# Brick_Doc_02.net
KiCad netlist of a schematic drawn in EAGLE
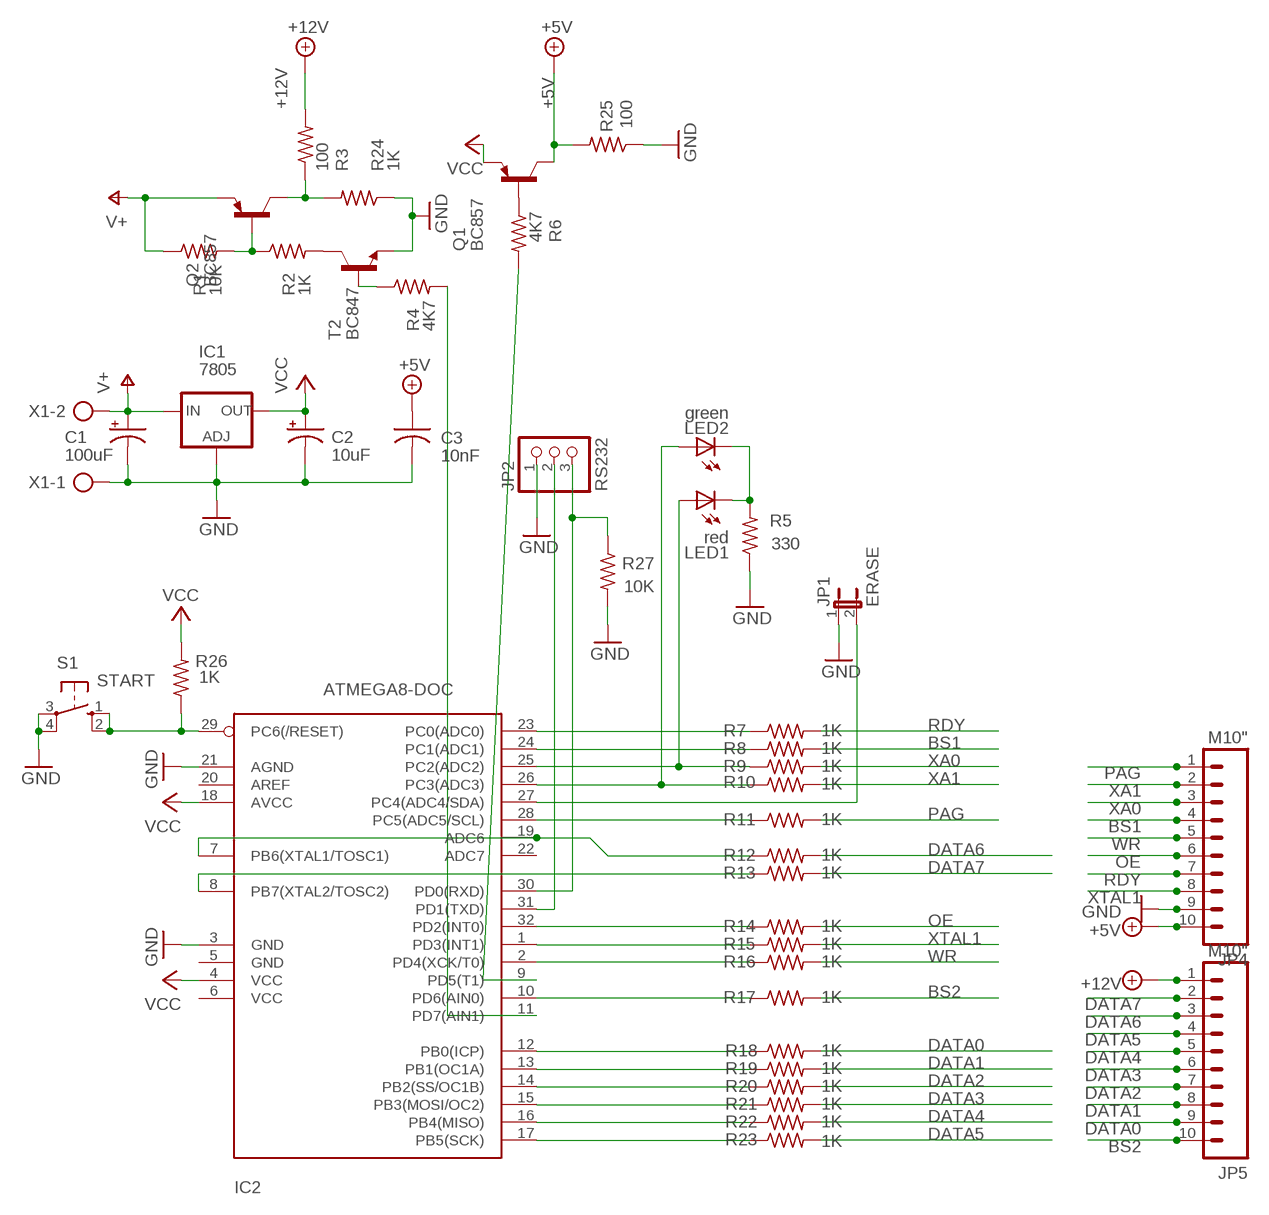
[diagram p0: schematic, sheet 1]

(export (version "E")
  (design (tool "Eeschema 10.0.6"))
  (components
    (comp (ref "C1")
      (value "100uF")
      (footprint "eagle-import:EIA3216")
      (libsource (lib "eagle-import") (part "CAP_POL1206"))
    )
    (comp (ref "C2")
      (value "10uF")
      (footprint "eagle-import:EIA3216")
      (libsource (lib "eagle-import") (part "CAP_POL1206"))
    )
    (comp (ref "C3")
      (value "10nF")
      (footprint "eagle-import:C0805")
      (libsource (lib "eagle-import") (part "C-USC0805"))
    )
    (comp (ref "IC1")
      (value "7805")
      (footprint "eagle-import:V-REG_DPACK")
      (libsource (lib "eagle-import") (part "V_REG_317DPACK"))
    )
    (comp (ref "IC2")
      (value "ATMEGA8-DOC")
      (footprint "eagle-import:TQFP32-08")
      (libsource (lib "eagle-import") (part "AVR-MEGA8-AI"))
    )
    (comp (ref "JP1")
      (value "ERASE")
      (footprint "eagle-import:JP1")
      (libsource (lib "eagle-import") (part "JP1E"))
    )
    (comp (ref "JP2")
      (value "RS232")
      (footprint "eagle-import:1X03")
      (libsource (lib "eagle-import") (part "PINHD-1X3"))
    )
    (comp (ref "JP4")
      (value "M10\"")
      (footprint "eagle-import:1X10")
      (libsource (lib "eagle-import") (part "M10{dblquote}"))
    )
    (comp (ref "JP5")
      (value "M10\"")
      (footprint "eagle-import:1X10")
      (libsource (lib "eagle-import") (part "M10{dblquote}"))
    )
    (comp (ref "LED1")
      (value "red")
      (footprint "eagle-import:SML0603")
      (libsource (lib "eagle-import") (part "LEDSML0603"))
    )
    (comp (ref "LED2")
      (value "green")
      (footprint "eagle-import:SML0603")
      (libsource (lib "eagle-import") (part "LEDSML0603"))
    )
    (comp (ref "Q1")
      (value "BC857")
      (footprint "eagle-import:SOT23-BEC")
      (libsource (lib "eagle-import") (part "BC857SMDALT1"))
    )
    (comp (ref "Q2")
      (value "BC857")
      (footprint "eagle-import:SOT23-BEC")
      (libsource (lib "eagle-import") (part "BC857SMDALT1"))
    )
    (comp (ref "R1")
      (value "10K")
      (footprint "eagle-import:R0805")
      (libsource (lib "eagle-import") (part "R-US_R0805"))
    )
    (comp (ref "R2")
      (value "1K")
      (footprint "eagle-import:R0805")
      (libsource (lib "eagle-import") (part "R-US_R0805"))
    )
    (comp (ref "R3")
      (value "100")
      (footprint "eagle-import:R0805")
      (libsource (lib "eagle-import") (part "R-US_R0805"))
    )
    (comp (ref "R4")
      (value "4K7")
      (footprint "eagle-import:R0805")
      (libsource (lib "eagle-import") (part "R-US_R0805"))
    )
    (comp (ref "R5")
      (value "330")
      (footprint "eagle-import:R0805")
      (libsource (lib "eagle-import") (part "R-US_R0805"))
    )
    (comp (ref "R6")
      (value "4K7")
      (footprint "eagle-import:R0805")
      (libsource (lib "eagle-import") (part "R-US_R0805"))
    )
    (comp (ref "R7")
      (value "1K")
      (footprint "eagle-import:R0805")
      (libsource (lib "eagle-import") (part "R-US_R0805"))
    )
    (comp (ref "R8")
      (value "1K")
      (footprint "eagle-import:R0805")
      (libsource (lib "eagle-import") (part "R-US_R0805"))
    )
    (comp (ref "R9")
      (value "1K")
      (footprint "eagle-import:R0805")
      (libsource (lib "eagle-import") (part "R-US_R0805"))
    )
    (comp (ref "R10")
      (value "1K")
      (footprint "eagle-import:R0805")
      (libsource (lib "eagle-import") (part "R-US_R0805"))
    )
    (comp (ref "R11")
      (value "1K")
      (footprint "eagle-import:R0805")
      (libsource (lib "eagle-import") (part "R-US_R0805"))
    )
    (comp (ref "R12")
      (value "1K")
      (footprint "eagle-import:R0805")
      (libsource (lib "eagle-import") (part "R-US_R0805"))
    )
    (comp (ref "R13")
      (value "1K")
      (footprint "eagle-import:R0805")
      (libsource (lib "eagle-import") (part "R-US_R0805"))
    )
    (comp (ref "R14")
      (value "1K")
      (footprint "eagle-import:R0805")
      (libsource (lib "eagle-import") (part "R-US_R0805"))
    )
    (comp (ref "R15")
      (value "1K")
      (footprint "eagle-import:R0805")
      (libsource (lib "eagle-import") (part "R-US_R0805"))
    )
    (comp (ref "R16")
      (value "1K")
      (footprint "eagle-import:R0805")
      (libsource (lib "eagle-import") (part "R-US_R0805"))
    )
    (comp (ref "R17")
      (value "1K")
      (footprint "eagle-import:R0805")
      (libsource (lib "eagle-import") (part "R-US_R0805"))
    )
    (comp (ref "R18")
      (value "1K")
      (footprint "eagle-import:R0805")
      (libsource (lib "eagle-import") (part "R-US_R0805"))
    )
    (comp (ref "R19")
      (value "1K")
      (footprint "eagle-import:R0805")
      (libsource (lib "eagle-import") (part "R-US_R0805"))
    )
    (comp (ref "R20")
      (value "1K")
      (footprint "eagle-import:R0805")
      (libsource (lib "eagle-import") (part "R-US_R0805"))
    )
    (comp (ref "R21")
      (value "1K")
      (footprint "eagle-import:R0805")
      (libsource (lib "eagle-import") (part "R-US_R0805"))
    )
    (comp (ref "R22")
      (value "1K")
      (footprint "eagle-import:R0805")
      (libsource (lib "eagle-import") (part "R-US_R0805"))
    )
    (comp (ref "R23")
      (value "1K")
      (footprint "eagle-import:R0805")
      (libsource (lib "eagle-import") (part "R-US_R0805"))
    )
    (comp (ref "R24")
      (value "1K")
      (footprint "eagle-import:R0805")
      (libsource (lib "eagle-import") (part "R-US_R0805"))
    )
    (comp (ref "R25")
      (value "100")
      (footprint "eagle-import:R0805")
      (libsource (lib "eagle-import") (part "R-US_R0805"))
    )
    (comp (ref "R26")
      (value "1K")
      (footprint "eagle-import:R0805")
      (libsource (lib "eagle-import") (part "R-US_R0805"))
    )
    (comp (ref "R27")
      (value "10K")
      (footprint "eagle-import:R0805")
      (libsource (lib "eagle-import") (part "R-US_R0805"))
    )
    (comp (ref "S1")
      (value "START")
      (footprint "eagle-import:B3F-10XX")
      (libsource (lib "eagle-import") (part "10-XX"))
    )
    (comp (ref "T2")
      (value "BC847")
      (footprint "eagle-import:SOT23")
      (libsource (lib "eagle-import") (part "BC847"))
    )
    (comp (ref "X1")
      (value "AK500/2")
      (footprint "eagle-import:AK500_2")
      (libsource (lib "eagle-import") (part "AK500/2"))
    )
  )
  (nets
    (net (code "1") (name "+5V") (class "Default")
      (node (ref "C3") (pin "1") (pinfunction "1_1") (pintype "passive"))
      (node (ref "JP4") (pin "10") (pinfunction "10_10") (pintype "passive"))
      (node (ref "Q1") (pin "C") (pinfunction "C_C") (pintype "passive"))
      (node (ref "R25") (pin "2") (pinfunction "2_2") (pintype "passive"))
    )
    (net (code "2") (name "+12V") (class "Default")
      (node (ref "JP5") (pin "1") (pinfunction "1_1") (pintype "passive"))
      (node (ref "R3") (pin "2") (pinfunction "2_2") (pintype "passive"))
    )
    (net (code "3") (name "/BS1") (class "Default")
      (node (ref "JP4") (pin "4") (pinfunction "4_4") (pintype "passive"))
      (node (ref "R8") (pin "2") (pinfunction "2_2") (pintype "passive"))
    )
    (net (code "4") (name "/BS2") (class "Default")
      (node (ref "JP5") (pin "10") (pinfunction "10_10") (pintype "passive"))
      (node (ref "R17") (pin "2") (pinfunction "2_2") (pintype "passive"))
    )
    (net (code "5") (name "/DATA0") (class "Default")
      (node (ref "JP5") (pin "9") (pinfunction "9_9") (pintype "passive"))
      (node (ref "R18") (pin "2") (pinfunction "2_2") (pintype "passive"))
    )
    (net (code "6") (name "/DATA1") (class "Default")
      (node (ref "JP5") (pin "8") (pinfunction "8_8") (pintype "passive"))
      (node (ref "R19") (pin "2") (pinfunction "2_2") (pintype "passive"))
    )
    (net (code "7") (name "/DATA2") (class "Default")
      (node (ref "JP5") (pin "7") (pinfunction "7_7") (pintype "passive"))
      (node (ref "R20") (pin "2") (pinfunction "2_2") (pintype "passive"))
    )
    (net (code "8") (name "/DATA3") (class "Default")
      (node (ref "JP5") (pin "6") (pinfunction "6_6") (pintype "passive"))
      (node (ref "R21") (pin "2") (pinfunction "2_2") (pintype "passive"))
    )
    (net (code "9") (name "/DATA4") (class "Default")
      (node (ref "JP5") (pin "5") (pinfunction "5_5") (pintype "passive"))
      (node (ref "R22") (pin "2") (pinfunction "2_2") (pintype "passive"))
    )
    (net (code "10") (name "/DATA5") (class "Default")
      (node (ref "JP5") (pin "4") (pinfunction "4_4") (pintype "passive"))
      (node (ref "R23") (pin "2") (pinfunction "2_2") (pintype "passive"))
    )
    (net (code "11") (name "/DATA6") (class "Default")
      (node (ref "JP5") (pin "3") (pinfunction "3_3") (pintype "passive"))
      (node (ref "R12") (pin "2") (pinfunction "2_2") (pintype "passive"))
    )
    (net (code "12") (name "/DATA7") (class "Default")
      (node (ref "JP5") (pin "2") (pinfunction "2_2") (pintype "passive"))
      (node (ref "R13") (pin "2") (pinfunction "2_2") (pintype "passive"))
    )
    (net (code "13") (name "/OE") (class "Default")
      (node (ref "JP4") (pin "6") (pinfunction "6_6") (pintype "passive"))
      (node (ref "R14") (pin "2") (pinfunction "2_2") (pintype "passive"))
    )
    (net (code "14") (name "/PAG") (class "Default")
      (node (ref "JP4") (pin "1") (pinfunction "1_1") (pintype "passive"))
      (node (ref "R11") (pin "2") (pinfunction "2_2") (pintype "passive"))
    )
    (net (code "15") (name "/RDY") (class "Default")
      (node (ref "JP4") (pin "7") (pinfunction "7_7") (pintype "passive"))
      (node (ref "R7") (pin "2") (pinfunction "2_2") (pintype "passive"))
    )
    (net (code "16") (name "/WR") (class "Default")
      (node (ref "JP4") (pin "5") (pinfunction "5_5") (pintype "passive"))
      (node (ref "R16") (pin "2") (pinfunction "2_2") (pintype "passive"))
    )
    (net (code "17") (name "/XA0") (class "Default")
      (node (ref "JP4") (pin "3") (pinfunction "3_3") (pintype "passive"))
      (node (ref "R9") (pin "2") (pinfunction "2_2") (pintype "passive"))
    )
    (net (code "18") (name "/XA1") (class "Default")
      (node (ref "JP4") (pin "2") (pinfunction "2_2") (pintype "passive"))
      (node (ref "R10") (pin "2") (pinfunction "2_2") (pintype "passive"))
    )
    (net (code "19") (name "/XTAL1") (class "Default")
      (node (ref "JP4") (pin "8") (pinfunction "8_8") (pintype "passive"))
      (node (ref "R15") (pin "2") (pinfunction "2_2") (pintype "passive"))
    )
    (net (code "20") (name "GND") (class "Default")
      (node (ref "C1") (pin "C") (pinfunction "-_C") (pintype "passive"))
      (node (ref "C2") (pin "C") (pinfunction "-_C") (pintype "passive"))
      (node (ref "C3") (pin "2") (pinfunction "2_2") (pintype "passive"))
      (node (ref "IC1") (pin "1") (pinfunction "ADJ_1") (pintype "input"))
      (node (ref "IC2") (pin "21") (pinfunction "AGND_21") (pintype "bidirectional"))
      (node (ref "IC2") (pin "3") (pinfunction "GND_3") (pintype "bidirectional"))
      (node (ref "JP1") (pin "1") (pinfunction "1_1") (pintype "passive"))
      (node (ref "JP2") (pin "1") (pinfunction "1_1") (pintype "passive"))
      (node (ref "JP4") (pin "9") (pinfunction "9_9") (pintype "passive"))
      (node (ref "R24") (pin "1") (pinfunction "1_1") (pintype "passive"))
      (node (ref "R25") (pin "1") (pinfunction "1_1") (pintype "passive"))
      (node (ref "R27") (pin "2") (pinfunction "2_2") (pintype "passive"))
      (node (ref "R5") (pin "1") (pinfunction "1_1") (pintype "passive"))
      (node (ref "S1") (pin "3") (pinfunction "P_3") (pintype "passive"))
      (node (ref "S1") (pin "4") (pinfunction "P1_4") (pintype "passive"))
      (node (ref "T2") (pin "2") (pinfunction "E_2") (pintype "passive"))
      (node (ref "X1") (pin "1") (pinfunction "KL_1") (pintype "passive"))
    )
    (net (code "21") (name "Net-(IC2-ADC6)") (class "Default")
      (node (ref "IC2") (pin "19") (pinfunction "ADC6_19") (pintype "bidirectional"))
      (node (ref "IC2") (pin "7") (pinfunction "PB6(XTAL1/TOSC1)_7") (pintype "bidirectional"))
      (node (ref "R12") (pin "1") (pinfunction "1_1") (pintype "passive"))
    )
    (net (code "22") (name "Net-(IC2-PB0(ICP))") (class "Default")
      (node (ref "IC2") (pin "12") (pinfunction "PB0(ICP)_12") (pintype "bidirectional"))
      (node (ref "R18") (pin "1") (pinfunction "1_1") (pintype "passive"))
    )
    (net (code "23") (name "Net-(IC2-PB1(OC1A))") (class "Default")
      (node (ref "IC2") (pin "13") (pinfunction "PB1(OC1A)_13") (pintype "bidirectional"))
      (node (ref "R19") (pin "1") (pinfunction "1_1") (pintype "passive"))
    )
    (net (code "24") (name "Net-(IC2-PB2(SS{slash}OC1B))") (class "Default")
      (node (ref "IC2") (pin "14") (pinfunction "PB2(SS/OC1B)_14") (pintype "bidirectional"))
      (node (ref "R20") (pin "1") (pinfunction "1_1") (pintype "passive"))
    )
    (net (code "25") (name "Net-(IC2-PB3(MOSI{slash}OC2))") (class "Default")
      (node (ref "IC2") (pin "15") (pinfunction "PB3(MOSI/OC2)_15") (pintype "bidirectional"))
      (node (ref "R21") (pin "1") (pinfunction "1_1") (pintype "passive"))
    )
    (net (code "26") (name "Net-(IC2-PB4(MISO))") (class "Default")
      (node (ref "IC2") (pin "16") (pinfunction "PB4(MISO)_16") (pintype "bidirectional"))
      (node (ref "R22") (pin "1") (pinfunction "1_1") (pintype "passive"))
    )
    (net (code "27") (name "Net-(IC2-PB5(SCK))") (class "Default")
      (node (ref "IC2") (pin "17") (pinfunction "PB5(SCK)_17") (pintype "bidirectional"))
      (node (ref "R23") (pin "1") (pinfunction "1_1") (pintype "passive"))
    )
    (net (code "28") (name "Net-(IC2-PB7(XTAL2{slash}TOSC2))") (class "Default")
      (node (ref "IC2") (pin "8") (pinfunction "PB7(XTAL2/TOSC2)_8") (pintype "bidirectional"))
      (node (ref "R13") (pin "1") (pinfunction "1_1") (pintype "passive"))
    )
    (net (code "29") (name "Net-(IC2-PC0(ADC0))") (class "Default")
      (node (ref "IC2") (pin "23") (pinfunction "PC0(ADC0)_23") (pintype "bidirectional"))
      (node (ref "R7") (pin "1") (pinfunction "1_1") (pintype "passive"))
    )
    (net (code "30") (name "Net-(IC2-PC1(ADC1))") (class "Default")
      (node (ref "IC2") (pin "24") (pinfunction "PC1(ADC1)_24") (pintype "bidirectional"))
      (node (ref "R8") (pin "1") (pinfunction "1_1") (pintype "passive"))
    )
    (net (code "31") (name "Net-(IC2-PC2(ADC2))") (class "Default")
      (node (ref "IC2") (pin "25") (pinfunction "PC2(ADC2)_25") (pintype "bidirectional"))
      (node (ref "LED1") (pin "A") (pinfunction "A_A") (pintype "passive"))
      (node (ref "R9") (pin "1") (pinfunction "1_1") (pintype "passive"))
    )
    (net (code "32") (name "Net-(IC2-PC3(ADC3))") (class "Default")
      (node (ref "IC2") (pin "26") (pinfunction "PC3(ADC3)_26") (pintype "bidirectional"))
      (node (ref "LED2") (pin "A") (pinfunction "A_A") (pintype "passive"))
      (node (ref "R10") (pin "1") (pinfunction "1_1") (pintype "passive"))
    )
    (net (code "33") (name "Net-(IC2-PC4(ADC4{slash}SDA))") (class "Default")
      (node (ref "IC2") (pin "27") (pinfunction "PC4(ADC4/SDA)_27") (pintype "bidirectional"))
      (node (ref "JP1") (pin "2") (pinfunction "2_2") (pintype "passive"))
    )
    (net (code "34") (name "Net-(IC2-PC5(ADC5{slash}SCL))") (class "Default")
      (node (ref "IC2") (pin "28") (pinfunction "PC5(ADC5/SCL)_28") (pintype "bidirectional"))
      (node (ref "R11") (pin "1") (pinfunction "1_1") (pintype "passive"))
    )
    (net (code "35") (name "Net-(IC2-PC6({slash}RESET))") (class "Default")
      (node (ref "IC2") (pin "29") (pinfunction "PC6(/RESET)_29") (pintype "bidirectional"))
      (node (ref "R26") (pin "1") (pinfunction "1_1") (pintype "passive"))
      (node (ref "S1") (pin "1") (pinfunction "S_1") (pintype "passive"))
      (node (ref "S1") (pin "2") (pinfunction "S1_2") (pintype "passive"))
    )
    (net (code "36") (name "Net-(IC2-PD0(RXD))") (class "Default")
      (node (ref "IC2") (pin "30") (pinfunction "PD0(RXD)_30") (pintype "bidirectional"))
      (node (ref "JP2") (pin "3") (pinfunction "3_3") (pintype "passive"))
      (node (ref "R27") (pin "1") (pinfunction "1_1") (pintype "passive"))
    )
    (net (code "37") (name "Net-(IC2-PD1(TXD))") (class "Default")
      (node (ref "IC2") (pin "31") (pinfunction "PD1(TXD)_31") (pintype "bidirectional"))
      (node (ref "JP2") (pin "2") (pinfunction "2_2") (pintype "passive"))
    )
    (net (code "38") (name "Net-(IC2-PD2(INT0))") (class "Default")
      (node (ref "IC2") (pin "32") (pinfunction "PD2(INT0)_32") (pintype "bidirectional"))
      (node (ref "R14") (pin "1") (pinfunction "1_1") (pintype "passive"))
    )
    (net (code "39") (name "Net-(IC2-PD3(INT1))") (class "Default")
      (node (ref "IC2") (pin "1") (pinfunction "PD3(INT1)_1") (pintype "bidirectional"))
      (node (ref "R15") (pin "1") (pinfunction "1_1") (pintype "passive"))
    )
    (net (code "40") (name "Net-(IC2-PD4(XCK{slash}T0))") (class "Default")
      (node (ref "IC2") (pin "2") (pinfunction "PD4(XCK/T0)_2") (pintype "bidirectional"))
      (node (ref "R16") (pin "1") (pinfunction "1_1") (pintype "passive"))
    )
    (net (code "41") (name "Net-(IC2-PD5(T1))") (class "Default")
      (node (ref "IC2") (pin "9") (pinfunction "PD5(T1)_9") (pintype "bidirectional"))
      (node (ref "R6") (pin "2") (pinfunction "2_2") (pintype "passive"))
    )
    (net (code "42") (name "Net-(IC2-PD6(AIN0))") (class "Default")
      (node (ref "IC2") (pin "10") (pinfunction "PD6(AIN0)_10") (pintype "bidirectional"))
      (node (ref "R17") (pin "1") (pinfunction "1_1") (pintype "passive"))
    )
    (net (code "43") (name "Net-(IC2-PD7(AIN1))") (class "Default")
      (node (ref "IC2") (pin "11") (pinfunction "PD7(AIN1)_11") (pintype "bidirectional"))
      (node (ref "R4") (pin "2") (pinfunction "2_2") (pintype "passive"))
    )
    (net (code "44") (name "Net-(LED1-PadC)") (class "Default")
      (node (ref "LED1") (pin "C") (pinfunction "C_C") (pintype "passive"))
      (node (ref "LED2") (pin "C") (pinfunction "C_C") (pintype "passive"))
      (node (ref "R5") (pin "2") (pinfunction "2_2") (pintype "passive"))
    )
    (net (code "45") (name "Net-(Q1-PadB)") (class "Default")
      (node (ref "Q1") (pin "B") (pinfunction "B_B") (pintype "passive"))
      (node (ref "R6") (pin "1") (pinfunction "1_1") (pintype "passive"))
    )
    (net (code "46") (name "Net-(Q2-PadB)") (class "Default")
      (node (ref "Q2") (pin "B") (pinfunction "B_B") (pintype "passive"))
      (node (ref "R1") (pin "2") (pinfunction "2_2") (pintype "passive"))
      (node (ref "R2") (pin "1") (pinfunction "1_1") (pintype "passive"))
    )
    (net (code "47") (name "Net-(Q2-PadC)") (class "Default")
      (node (ref "Q2") (pin "C") (pinfunction "C_C") (pintype "passive"))
      (node (ref "R24") (pin "2") (pinfunction "2_2") (pintype "passive"))
      (node (ref "R3") (pin "1") (pinfunction "1_1") (pintype "passive"))
    )
    (net (code "48") (name "Net-(T2-B)") (class "Default")
      (node (ref "R4") (pin "1") (pinfunction "1_1") (pintype "passive"))
      (node (ref "T2") (pin "1") (pinfunction "B_1") (pintype "passive"))
    )
    (net (code "49") (name "Net-(T2-C)") (class "Default")
      (node (ref "R2") (pin "2") (pinfunction "2_2") (pintype "passive"))
      (node (ref "T2") (pin "3") (pinfunction "C_3") (pintype "passive"))
    )
    (net (code "50") (name "V+") (class "Default")
      (node (ref "C1") (pin "A") (pinfunction "+_A") (pintype "passive"))
      (node (ref "IC1") (pin "3") (pinfunction "IN_3") (pintype "input"))
      (node (ref "Q2") (pin "E") (pinfunction "E_E") (pintype "passive"))
      (node (ref "R1") (pin "1") (pinfunction "1_1") (pintype "passive"))
      (node (ref "X1") (pin "2") (pinfunction "KL_2") (pintype "passive"))
    )
    (net (code "51") (name "VCC") (class "Default")
      (node (ref "C2") (pin "A") (pinfunction "+_A") (pintype "passive"))
      (node (ref "IC1") (pin "4") (pinfunction "OUT_4") (pintype "output"))
      (node (ref "IC2") (pin "18") (pinfunction "AVCC_18") (pintype "bidirectional"))
      (node (ref "IC2") (pin "4") (pinfunction "VCC_4") (pintype "bidirectional"))
      (node (ref "Q1") (pin "E") (pinfunction "E_E") (pintype "passive"))
      (node (ref "R26") (pin "2") (pinfunction "2_2") (pintype "passive"))
    )
    (net (code "52") (name "unconnected-(IC2-ADC7-Pad22)") (class "Default")
      (node (ref "IC2") (pin "22") (pinfunction "ADC7_22") (pintype "bidirectional"))
    )
    (net (code "53") (name "unconnected-(IC2-AREF-Pad20)") (class "Default")
      (node (ref "IC2") (pin "20") (pinfunction "AREF_20") (pintype "bidirectional"))
    )
    (net (code "54") (name "unconnected-(IC2-GND-Pad5)") (class "Default")
      (node (ref "IC2") (pin "5") (pinfunction "GND_5") (pintype "bidirectional"))
    )
    (net (code "55") (name "unconnected-(IC2-VCC-Pad6)") (class "Default")
      (node (ref "IC2") (pin "6") (pinfunction "VCC_6") (pintype "bidirectional"))
    )
  )
)
